# cherry-u2f.net
KiCad netlist of a schematic drawn in EAGLE
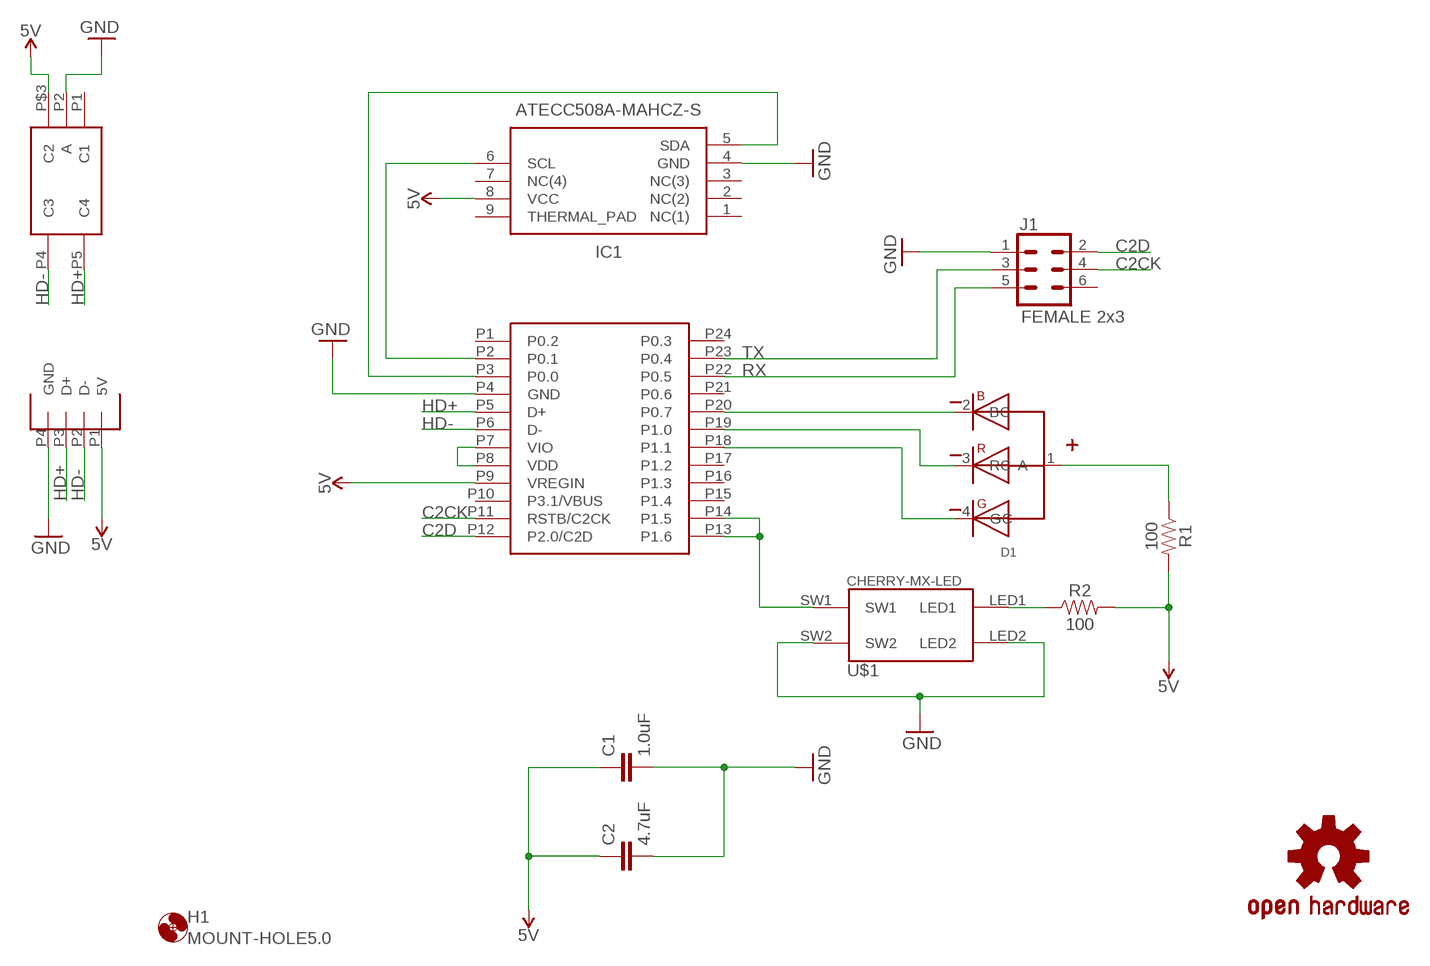
[diagram p0: schematic, sheet 1]

(export (version "E")
  (design (tool "Eeschema 10.0.6"))
  (components
    (comp (ref "C1")
      (value "1.0uF")
      (footprint "eagle-import:0603")
      (libsource (lib "eagle-import") (part "1.0UF-0603-16V-10%"))
    )
    (comp (ref "C2")
      (value "4.7uF")
      (footprint "eagle-import:0603")
      (libsource (lib "eagle-import") (part "4.7UF0603"))
    )
    (comp (ref "D1")
      (value "WL-SFTW-150141M173100-R&G&B")
      (footprint "eagle-import:WL-SFTW_3528")
      (libsource (lib "eagle-import") (part "WL-SFTW-150141M173100-R&G&B"))
    )
    (comp (ref "H1")
      (value "MOUNT-HOLE5.0")
      (footprint "eagle-import:5,0")
      (libsource (lib "eagle-import") (part "MOUNT-HOLE5.0"))
    )
    (comp (ref "IC1")
      (value "ATECC508A-MAHCZ-S")
      (footprint "eagle-import:SON50P300X200X60-9N")
      (libsource (lib "eagle-import") (part "ATECC508A-MAHCZ-S"))
    )
    (comp (ref "J1")
      (value "FEMALE 2x3")
      (footprint "eagle-import:2X3")
      (libsource (lib "eagle-import") (part "CONN_03X2FEMALE"))
    )
    (comp (ref "LOGO1")
      (value "OSHW-LOGOS")
      (footprint "eagle-import:OSHW-LOGO-S")
      (libsource (lib "eagle-import") (part "OSHW-LOGOS"))
    )
    (comp (ref "R1")
      (value "100")
      (footprint "eagle-import:0603")
      (libsource (lib "eagle-import") (part "100OHM-0603-1/4W-5%"))
    )
    (comp (ref "R2")
      (value "100")
      (footprint "eagle-import:0603")
      (libsource (lib "eagle-import") (part "100OHM-0603-1/4W-5%"))
    )
    (comp (ref "U$1")
      (value "CHERRY-MX-LED")
      (footprint "eagle-import:CHERRY-MX-LED")
      (libsource (lib "eagle-import") (part "CHERRY-MX-LED"))
    )
    (comp (ref "U$2")
      (value "EFM8UB1-QSOP24")
      (footprint "eagle-import:QSOP24")
      (libsource (lib "eagle-import") (part "EFM8UB1-QSOP24"))
    )
    (comp (ref "U$3")
      (value "DF5A5.6JE")
      (footprint "eagle-import:DF5A5.6JE")
      (libsource (lib "eagle-import") (part "DF5A5.6JE"))
    )
    (comp (ref "U$4")
      (value "USB-A-PCB")
      (footprint "eagle-import:USB-A-PCB")
      (libsource (lib "eagle-import") (part "USB-A-PCB"))
    )
  )
  (nets
    (net (code "1") (name "/C2CK") (class "Default")
      (node (ref "J1") (pin "4") (pinfunction "4_4") (pintype "bidirectional"))
      (node (ref "U$2") (pin "P11") (pinfunction "RSTB/C2CK_P11") (pintype "bidirectional"))
    )
    (net (code "2") (name "/C2D") (class "Default")
      (node (ref "J1") (pin "2") (pinfunction "2_2") (pintype "bidirectional"))
      (node (ref "U$2") (pin "P12") (pinfunction "P2.0/C2D_P12") (pintype "bidirectional"))
    )
    (net (code "3") (name "/HD+") (class "Default")
      (node (ref "U$2") (pin "P5") (pinfunction "D+_P5") (pintype "bidirectional"))
      (node (ref "U$3") (pin "P5") (pinfunction "C4_P5") (pintype "bidirectional"))
      (node (ref "U$4") (pin "P3") (pinfunction "D+_P3") (pintype "bidirectional"))
    )
    (net (code "4") (name "/HD-") (class "Default")
      (node (ref "U$2") (pin "P6") (pinfunction "D-_P6") (pintype "bidirectional"))
      (node (ref "U$3") (pin "P4") (pinfunction "C3_P4") (pintype "bidirectional"))
      (node (ref "U$4") (pin "P2") (pinfunction "D-_P2") (pintype "bidirectional"))
    )
    (net (code "5") (name "/RX") (class "Default")
      (node (ref "J1") (pin "5") (pinfunction "5_5") (pintype "bidirectional"))
      (node (ref "U$2") (pin "P22") (pinfunction "P0.5_P22") (pintype "bidirectional"))
    )
    (net (code "6") (name "/TX") (class "Default")
      (node (ref "J1") (pin "3") (pinfunction "3_3") (pintype "bidirectional"))
      (node (ref "U$2") (pin "P23") (pinfunction "P0.4_P23") (pintype "bidirectional"))
    )
    (net (code "7") (name "5V") (class "Default")
      (node (ref "C1") (pin "1") (pinfunction "1_1") (pintype "passive"))
      (node (ref "C2") (pin "1") (pinfunction "1_1") (pintype "passive"))
      (node (ref "IC1") (pin "8") (pinfunction "VCC_8") (pintype "passive"))
      (node (ref "R1") (pin "2") (pinfunction "2_2") (pintype "passive"))
      (node (ref "R2") (pin "2") (pinfunction "2_2") (pintype "passive"))
      (node (ref "U$2") (pin "P9") (pinfunction "VREGIN_P9") (pintype "bidirectional"))
      (node (ref "U$3") (pin "P$3") (pinfunction "C2_P$3") (pintype "bidirectional"))
      (node (ref "U$4") (pin "P1") (pinfunction "5V_P1") (pintype "bidirectional"))
    )
    (net (code "8") (name "GND") (class "Default")
      (node (ref "C1") (pin "2") (pinfunction "2_2") (pintype "passive"))
      (node (ref "C2") (pin "2") (pinfunction "2_2") (pintype "passive"))
      (node (ref "IC1") (pin "4") (pinfunction "GND_4") (pintype "passive"))
      (node (ref "J1") (pin "1") (pinfunction "1_1") (pintype "bidirectional"))
      (node (ref "U$1") (pin "LED2") (pinfunction "LED2_LED2") (pintype "bidirectional"))
      (node (ref "U$1") (pin "SW2") (pinfunction "SW2_SW2") (pintype "bidirectional"))
      (node (ref "U$2") (pin "P4") (pinfunction "GND_P4") (pintype "bidirectional"))
      (node (ref "U$3") (pin "P2") (pinfunction "A_P2") (pintype "bidirectional"))
      (node (ref "U$4") (pin "P4") (pinfunction "GND_P4") (pintype "bidirectional"))
    )
    (net (code "9") (name "Net-(D1-A)") (class "Default")
      (node (ref "D1") (pin "1") (pinfunction "A_1") (pintype "passive"))
      (node (ref "R1") (pin "1") (pinfunction "1_1") (pintype "passive"))
    )
    (net (code "10") (name "Net-(D1-BC)") (class "Default")
      (node (ref "D1") (pin "2") (pinfunction "BC_2") (pintype "passive"))
      (node (ref "U$2") (pin "P20") (pinfunction "P0.7_P20") (pintype "bidirectional"))
    )
    (net (code "11") (name "Net-(D1-GC)") (class "Default")
      (node (ref "D1") (pin "4") (pinfunction "GC_4") (pintype "passive"))
      (node (ref "U$2") (pin "P18") (pinfunction "P1.1_P18") (pintype "bidirectional"))
    )
    (net (code "12") (name "Net-(D1-RC)") (class "Default")
      (node (ref "D1") (pin "3") (pinfunction "RC_3") (pintype "passive"))
      (node (ref "U$2") (pin "P19") (pinfunction "P1.0_P19") (pintype "bidirectional"))
    )
    (net (code "13") (name "Net-(IC1-SCL)") (class "Default")
      (node (ref "IC1") (pin "6") (pinfunction "SCL_6") (pintype "passive"))
      (node (ref "U$2") (pin "P2") (pinfunction "P0.1_P2") (pintype "bidirectional"))
    )
    (net (code "14") (name "Net-(IC1-SDA)") (class "Default")
      (node (ref "IC1") (pin "5") (pinfunction "SDA_5") (pintype "passive"))
      (node (ref "U$2") (pin "P3") (pinfunction "P0.0_P3") (pintype "bidirectional"))
    )
    (net (code "15") (name "Net-(R2-Pad1)") (class "Default")
      (node (ref "R2") (pin "1") (pinfunction "1_1") (pintype "passive"))
      (node (ref "U$1") (pin "LED1") (pinfunction "LED1_LED1") (pintype "bidirectional"))
    )
    (net (code "16") (name "Net-(U$2-P1.5)") (class "Default")
      (node (ref "U$1") (pin "SW1") (pinfunction "SW1_SW1") (pintype "bidirectional"))
      (node (ref "U$2") (pin "P13") (pinfunction "P1.6_P13") (pintype "bidirectional"))
      (node (ref "U$2") (pin "P14") (pinfunction "P1.5_P14") (pintype "bidirectional"))
    )
    (net (code "17") (name "Net-(U$2-VDD)") (class "Default")
      (node (ref "U$2") (pin "P7") (pinfunction "VIO_P7") (pintype "bidirectional"))
      (node (ref "U$2") (pin "P8") (pinfunction "VDD_P8") (pintype "bidirectional"))
    )
    (net (code "18") (name "unconnected-(IC1-NC(1)-Pad1)") (class "Default")
      (node (ref "IC1") (pin "1") (pinfunction "NC(1)_1") (pintype "passive"))
    )
    (net (code "19") (name "unconnected-(IC1-NC(2)-Pad2)") (class "Default")
      (node (ref "IC1") (pin "2") (pinfunction "NC(2)_2") (pintype "passive"))
    )
    (net (code "20") (name "unconnected-(IC1-NC(3)-Pad3)") (class "Default")
      (node (ref "IC1") (pin "3") (pinfunction "NC(3)_3") (pintype "passive"))
    )
    (net (code "21") (name "unconnected-(IC1-NC(4)-Pad7)") (class "Default")
      (node (ref "IC1") (pin "7") (pinfunction "NC(4)_7") (pintype "passive"))
    )
    (net (code "22") (name "unconnected-(IC1-THERMAL_PAD-Pad9)") (class "Default")
      (node (ref "IC1") (pin "9") (pinfunction "THERMAL_PAD_9") (pintype "passive"))
    )
    (net (code "23") (name "unconnected-(J1-Pad6)") (class "Default")
      (node (ref "J1") (pin "6") (pinfunction "6_6") (pintype "bidirectional"))
    )
    (net (code "24") (name "unconnected-(U$2-P0.2-PadP1)") (class "Default")
      (node (ref "U$2") (pin "P1") (pinfunction "P0.2_P1") (pintype "bidirectional"))
    )
    (net (code "25") (name "unconnected-(U$2-P0.3-PadP24)") (class "Default")
      (node (ref "U$2") (pin "P24") (pinfunction "P0.3_P24") (pintype "bidirectional"))
    )
    (net (code "26") (name "unconnected-(U$2-P0.6-PadP21)") (class "Default")
      (node (ref "U$2") (pin "P21") (pinfunction "P0.6_P21") (pintype "bidirectional"))
    )
    (net (code "27") (name "unconnected-(U$2-P1.2-PadP17)") (class "Default")
      (node (ref "U$2") (pin "P17") (pinfunction "P1.2_P17") (pintype "bidirectional"))
    )
    (net (code "28") (name "unconnected-(U$2-P1.3-PadP16)") (class "Default")
      (node (ref "U$2") (pin "P16") (pinfunction "P1.3_P16") (pintype "bidirectional"))
    )
    (net (code "29") (name "unconnected-(U$2-P1.4-PadP15)") (class "Default")
      (node (ref "U$2") (pin "P15") (pinfunction "P1.4_P15") (pintype "bidirectional"))
    )
    (net (code "30") (name "unconnected-(U$2-P3.1{slash}VBUS-PadP10)") (class "Default")
      (node (ref "U$2") (pin "P10") (pinfunction "P3.1/VBUS_P10") (pintype "bidirectional"))
    )
    (net (code "31") (name "unconnected-(U$3-C1-PadP1)") (class "Default")
      (node (ref "U$3") (pin "P1") (pinfunction "C1_P1") (pintype "bidirectional"))
    )
  )
)
